# Main_PCB.net
KiCad netlist of a schematic drawn in EAGLE
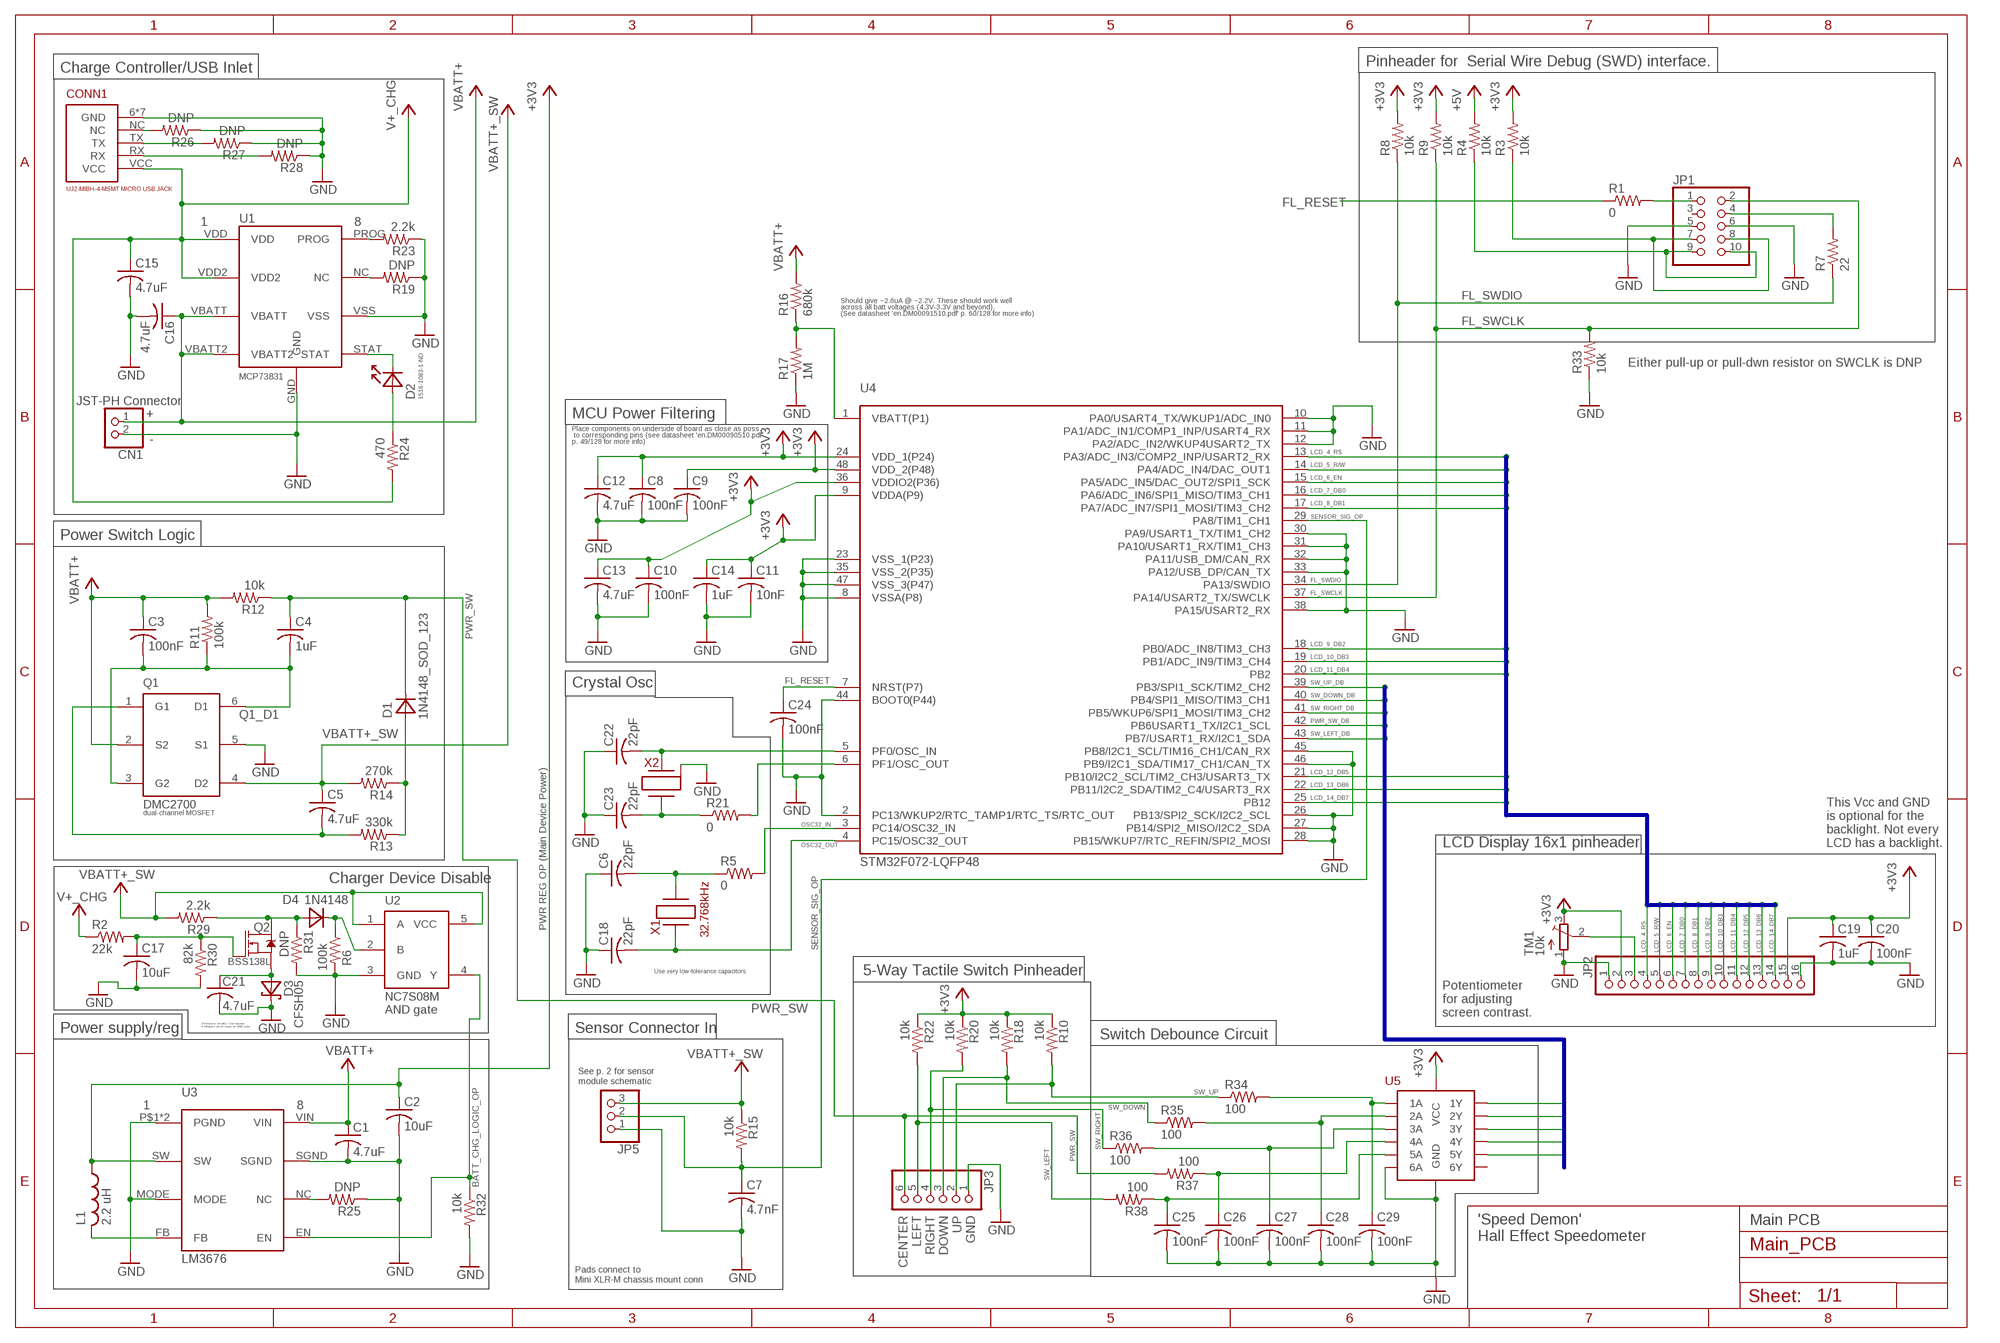
[diagram p0: schematic, sheet 1]

(export (version "E")
  (design (tool "Eeschema 10.0.6"))
  (components
    (comp (ref "C1")
      (value "4.7uF")
      (footprint "eagle-import:C_0805")
      (libsource (lib "eagle-import") (part "C_0805_NP"))
    )
    (comp (ref "C2")
      (value "10uF")
      (footprint "eagle-import:C_0805")
      (libsource (lib "eagle-import") (part "C_0805_NP"))
    )
    (comp (ref "C3")
      (value "100nF")
      (footprint "eagle-import:C_0805")
      (libsource (lib "eagle-import") (part "C_0805_NP"))
    )
    (comp (ref "C4")
      (value "1uF")
      (footprint "eagle-import:C_0805")
      (libsource (lib "eagle-import") (part "C_0805_NP"))
    )
    (comp (ref "C5")
      (value "4.7uF")
      (footprint "eagle-import:C_0805")
      (libsource (lib "eagle-import") (part "C_0805_NP"))
    )
    (comp (ref "C6")
      (value "22pF")
      (footprint "eagle-import:C_0805")
      (libsource (lib "eagle-import") (part "LCRD_SMD_generics_C_0805_NP"))
    )
    (comp (ref "C7")
      (value "4.7nF")
      (footprint "eagle-import:C_0805")
      (libsource (lib "eagle-import") (part "C_0805_NP"))
    )
    (comp (ref "C8")
      (value "100nF")
      (footprint "eagle-import:C_0805")
      (libsource (lib "eagle-import") (part "C_0805_NP"))
    )
    (comp (ref "C9")
      (value "100nF")
      (footprint "eagle-import:C_0805")
      (libsource (lib "eagle-import") (part "C_0805_NP"))
    )
    (comp (ref "C10")
      (value "100nF")
      (footprint "eagle-import:C_0805")
      (libsource (lib "eagle-import") (part "C_0805_NP"))
    )
    (comp (ref "C11")
      (value "10nF")
      (footprint "eagle-import:C_0805")
      (libsource (lib "eagle-import") (part "C_0805_NP"))
    )
    (comp (ref "C12")
      (value "4.7uF")
      (footprint "eagle-import:C_0805")
      (libsource (lib "eagle-import") (part "C_0805_NP"))
    )
    (comp (ref "C13")
      (value "4.7uF")
      (footprint "eagle-import:C_0805")
      (libsource (lib "eagle-import") (part "C_0805_NP"))
    )
    (comp (ref "C14")
      (value "1uF")
      (footprint "eagle-import:C_0805")
      (libsource (lib "eagle-import") (part "C_0805_NP"))
    )
    (comp (ref "C15")
      (value "4.7uF")
      (footprint "eagle-import:C_0805")
      (libsource (lib "eagle-import") (part "C_0805_NP"))
    )
    (comp (ref "C16")
      (value "4.7uF")
      (footprint "eagle-import:C_0805")
      (libsource (lib "eagle-import") (part "C_0805_NP"))
    )
    (comp (ref "C17")
      (value "10uF")
      (footprint "eagle-import:C_0805")
      (libsource (lib "eagle-import") (part "C_0805_NP"))
    )
    (comp (ref "C18")
      (value "22pF")
      (footprint "eagle-import:C_0805")
      (libsource (lib "eagle-import") (part "LCRD_SMD_generics_C_0805_NP"))
    )
    (comp (ref "C19")
      (value "1uF")
      (footprint "eagle-import:C_0805")
      (libsource (lib "eagle-import") (part "C_0805_NP"))
    )
    (comp (ref "C20")
      (value "100nF")
      (footprint "eagle-import:C_0805")
      (libsource (lib "eagle-import") (part "C_0805_NP"))
    )
    (comp (ref "C21")
      (value "4.7uF")
      (footprint "eagle-import:C_0805")
      (libsource (lib "eagle-import") (part "C_0805_NP"))
    )
    (comp (ref "C22")
      (value "22pF")
      (footprint "eagle-import:C_0805")
      (libsource (lib "eagle-import") (part "LCRD_SMD_generics_C_0805_NP"))
    )
    (comp (ref "C23")
      (value "22pF")
      (footprint "eagle-import:C_0805")
      (libsource (lib "eagle-import") (part "LCRD_SMD_generics_C_0805_NP"))
    )
    (comp (ref "C24")
      (value "100nF")
      (footprint "eagle-import:C_0805")
      (libsource (lib "eagle-import") (part "C_0805_NP"))
    )
    (comp (ref "C25")
      (value "100nF")
      (footprint "eagle-import:C_0805")
      (libsource (lib "eagle-import") (part "C_0805_NP"))
    )
    (comp (ref "C26")
      (value "100nF")
      (footprint "eagle-import:C_0805")
      (libsource (lib "eagle-import") (part "C_0805_NP"))
    )
    (comp (ref "C27")
      (value "100nF")
      (footprint "eagle-import:C_0805")
      (libsource (lib "eagle-import") (part "C_0805_NP"))
    )
    (comp (ref "C28")
      (value "100nF")
      (footprint "eagle-import:C_0805")
      (libsource (lib "eagle-import") (part "C_0805_NP"))
    )
    (comp (ref "C29")
      (value "100nF")
      (footprint "eagle-import:C_0805")
      (libsource (lib "eagle-import") (part "C_0805_NP"))
    )
    (comp (ref "CN1")
      (value "JST_2PIN-SMT-RA")
      (footprint "eagle-import:JST-PH-2-SMT-RA")
      (libsource (lib "eagle-import") (part "JST_2PIN-SMT-RA"))
    )
    (comp (ref "CONN1")
      (value "USB_JACK_102-4008-1-ND_USB-MICRO-B")
      (footprint "eagle-import:USB_JACK_102-4008-1-ND_UJ2-MIBH-4-MSMT-TR")
      (libsource (lib "eagle-import") (part "USB_JACK_102-4008-1-ND_USB-MICRO-B"))
    )
    (comp (ref "D1")
      (value "1N4148_SOD_123")
      (footprint "eagle-import:D_SOD_123")
      (libsource (lib "eagle-import") (part "1N4148_SOD_123"))
    )
    (comp (ref "D2")
      (value "LED_0805")
      (footprint "eagle-import:LED_0805")
      (libsource (lib "eagle-import") (part "LED_0805"))
    )
    (comp (ref "D3")
      (value "CFSH05")
      (footprint "eagle-import:SOD-882")
      (libsource (lib "eagle-import") (part "CFSH05_SCHOTTKY"))
    )
    (comp (ref "D4")
      (value "1N4148")
      (footprint "eagle-import:D_SOD_123")
      (libsource (lib "eagle-import") (part "1N4148_SOD_123"))
    )
    (comp (ref "JP1")
      (value "PINHD-2X5")
      (footprint "eagle-import:2X05")
      (libsource (lib "eagle-import") (part "PINHD-2X5"))
    )
    (comp (ref "JP2")
      (value "PINHD-1X16")
      (footprint "eagle-import:1X16")
      (libsource (lib "eagle-import") (part "PINHD-1X16"))
    )
    (comp (ref "JP3")
      (value "PINHD-1X6")
      (footprint "eagle-import:1X06")
      (libsource (lib "eagle-import") (part "PINHD-1X6"))
    )
    (comp (ref "JP5")
      (value "PINHD-1X3")
      (footprint "eagle-import:1X03")
      (libsource (lib "eagle-import") (part "PINHD-1X3"))
    )
    (comp (ref "L1")
      (value "2.2 uH")
      (footprint "eagle-import:NONSTANDARD_IND")
      (libsource (lib "eagle-import") (part "NRS4010T2R2MDGGV"))
    )
    (comp (ref "Q1")
      (value "DMC2700")
      (footprint "eagle-import:SOT-23-6")
      (libsource (lib "eagle-import") (part "DMC2700_SOT-23-6"))
    )
    (comp (ref "Q2")
      (value "BSS138L")
      (footprint "eagle-import:TO-236")
      (libsource (lib "eagle-import") (part "BSS138LT1_TO-236"))
    )
    (comp (ref "R1")
      (value "0")
      (footprint "eagle-import:R0805")
      (libsource (lib "eagle-import") (part "R-US_R0805"))
    )
    (comp (ref "R2")
      (value "22k")
      (footprint "eagle-import:R_0805")
      (libsource (lib "eagle-import") (part "R_0805"))
    )
    (comp (ref "R3")
      (value "10k")
      (footprint "eagle-import:R0805")
      (libsource (lib "eagle-import") (part "R-US_R0805"))
    )
    (comp (ref "R4")
      (value "10k")
      (footprint "eagle-import:R0805")
      (libsource (lib "eagle-import") (part "R-US_R0805"))
    )
    (comp (ref "R5")
      (value "0")
      (footprint "eagle-import:R0805")
      (libsource (lib "eagle-import") (part "R-US_R0805"))
    )
    (comp (ref "R6")
      (value "100k")
      (footprint "eagle-import:R_0805")
      (libsource (lib "eagle-import") (part "R_0805"))
    )
    (comp (ref "R7")
      (value "22")
      (footprint "eagle-import:R0805")
      (libsource (lib "eagle-import") (part "R-US_R0805"))
    )
    (comp (ref "R8")
      (value "10k")
      (footprint "eagle-import:R0805")
      (libsource (lib "eagle-import") (part "R-US_R0805"))
    )
    (comp (ref "R9")
      (value "10k")
      (footprint "eagle-import:R0805")
      (libsource (lib "eagle-import") (part "R-US_R0805"))
    )
    (comp (ref "R10")
      (value "10k")
      (footprint "eagle-import:R_0805")
      (libsource (lib "eagle-import") (part "R_0805"))
    )
    (comp (ref "R11")
      (value "100k")
      (footprint "eagle-import:R_0805")
      (libsource (lib "eagle-import") (part "R_0805"))
    )
    (comp (ref "R12")
      (value "10k")
      (footprint "eagle-import:R_0805")
      (libsource (lib "eagle-import") (part "R_0805"))
    )
    (comp (ref "R13")
      (value "330k")
      (footprint "eagle-import:R_0805")
      (libsource (lib "eagle-import") (part "R_0805"))
    )
    (comp (ref "R14")
      (value "270k")
      (footprint "eagle-import:R_0805")
      (libsource (lib "eagle-import") (part "R_0805"))
    )
    (comp (ref "R15")
      (value "10k")
      (footprint "eagle-import:R_0805")
      (libsource (lib "eagle-import") (part "R_0805"))
    )
    (comp (ref "R16")
      (value "680k")
      (footprint "eagle-import:R_0805")
      (libsource (lib "eagle-import") (part "R_0805"))
    )
    (comp (ref "R17")
      (value "1M")
      (footprint "eagle-import:R_0805")
      (libsource (lib "eagle-import") (part "R_0805"))
    )
    (comp (ref "R18")
      (value "10k")
      (footprint "eagle-import:R_0805")
      (libsource (lib "eagle-import") (part "R_0805"))
    )
    (comp (ref "R19")
      (value "DNP")
      (footprint "eagle-import:R_0805")
      (libsource (lib "eagle-import") (part "R_0805"))
    )
    (comp (ref "R20")
      (value "10k")
      (footprint "eagle-import:R_0805")
      (libsource (lib "eagle-import") (part "R_0805"))
    )
    (comp (ref "R21")
      (value "0")
      (footprint "eagle-import:R_0805")
      (libsource (lib "eagle-import") (part "LCRD_SMD_generics_R_0805"))
    )
    (comp (ref "R22")
      (value "10k")
      (footprint "eagle-import:R_0805")
      (libsource (lib "eagle-import") (part "R_0805"))
    )
    (comp (ref "R23")
      (value "2.2k")
      (footprint "eagle-import:R_0805")
      (libsource (lib "eagle-import") (part "R_0805"))
    )
    (comp (ref "R24")
      (value "470")
      (footprint "eagle-import:R_0805")
      (libsource (lib "eagle-import") (part "R_0805"))
    )
    (comp (ref "R25")
      (value "DNP")
      (footprint "eagle-import:R_0805")
      (libsource (lib "eagle-import") (part "R_0805"))
    )
    (comp (ref "R26")
      (value "DNP")
      (footprint "eagle-import:R_0805")
      (libsource (lib "eagle-import") (part "R_0805"))
    )
    (comp (ref "R27")
      (value "DNP")
      (footprint "eagle-import:R_0805")
      (libsource (lib "eagle-import") (part "R_0805"))
    )
    (comp (ref "R28")
      (value "DNP")
      (footprint "eagle-import:R_0805")
      (libsource (lib "eagle-import") (part "R_0805"))
    )
    (comp (ref "R29")
      (value "2.2k")
      (footprint "eagle-import:R_0805")
      (libsource (lib "eagle-import") (part "R_0805"))
    )
    (comp (ref "R30")
      (value "82k")
      (footprint "eagle-import:R_0805")
      (libsource (lib "eagle-import") (part "R_0805"))
    )
    (comp (ref "R31")
      (value "DNP")
      (footprint "eagle-import:R_0805")
      (libsource (lib "eagle-import") (part "R_0805"))
    )
    (comp (ref "R32")
      (value "10k")
      (footprint "eagle-import:R_0805")
      (libsource (lib "eagle-import") (part "R_0805"))
    )
    (comp (ref "R33")
      (value "10k")
      (footprint "eagle-import:R0805")
      (libsource (lib "eagle-import") (part "R-US_R0805"))
    )
    (comp (ref "R34")
      (value "100")
      (footprint "eagle-import:R_0805")
      (libsource (lib "eagle-import") (part "R_0805"))
    )
    (comp (ref "R35")
      (value "100")
      (footprint "eagle-import:R_0805")
      (libsource (lib "eagle-import") (part "R_0805"))
    )
    (comp (ref "R36")
      (value "100")
      (footprint "eagle-import:R_0805")
      (libsource (lib "eagle-import") (part "R_0805"))
    )
    (comp (ref "R37")
      (value "100")
      (footprint "eagle-import:R_0805")
      (libsource (lib "eagle-import") (part "R_0805"))
    )
    (comp (ref "R38")
      (value "100")
      (footprint "eagle-import:R_0805")
      (libsource (lib "eagle-import") (part "R_0805"))
    )
    (comp (ref "TM1")
      (value "10k")
      (footprint "eagle-import:TRIM-3386")
      (libsource (lib "eagle-import") (part "TRIMPOT3386"))
    )
    (comp (ref "U1")
      (value "MCP73831_8-DFN")
      (footprint "eagle-import:8-DFN-(2X3)")
      (libsource (lib "eagle-import") (part "MCP73831_8-DFN"))
    )
    (comp (ref "U2")
      (value "NC7S08M")
      (footprint "eagle-import:SOT-23-5")
      (libsource (lib "eagle-import") (part "NC7S08_SOT_23_5"))
    )
    (comp (ref "U3")
      (value "LM3676")
      (footprint "eagle-import:WSON")
      (libsource (lib "eagle-import") (part "LM3676"))
    )
    (comp (ref "U4")
      (value "STM32F072-LQFP48")
      (footprint "eagle-import:LQFP48")
      (libsource (lib "eagle-import") (part "STM32F072-LQFP48"))
    )
    (comp (ref "U5")
      (value "SN74LV14A_HEX_SHMITT")
      (footprint "eagle-import:S-PVFQN-N14")
      (libsource (lib "eagle-import") (part "SN74LV14A_HEX_SHMITT"))
    )
    (comp (ref "X1")
      (value "32.768kHz")
      (footprint "eagle-import:CRYSTAL_OSC_3.2X1.5")
      (libsource (lib "eagle-import") (part "XC2292CT-ND"))
    )
    (comp (ref "X2")
      (value "ABM3B-8.000MHZ-10-D-1-G-T")
      (footprint "eagle-import:4-SMD")
      (libsource (lib "eagle-import") (part "ABM3B-8.000MHZ-10-D-1-G-T"))
    )
  )
  (nets
    (net (code "1") (name "+3V3") (class "Default")
      (node (ref "C10") (pin "1") (pinfunction "1_1") (pintype "passive"))
      (node (ref "C11") (pin "1") (pinfunction "1_1") (pintype "passive"))
      (node (ref "C12") (pin "1") (pinfunction "1_1") (pintype "passive"))
      (node (ref "C13") (pin "1") (pinfunction "1_1") (pintype "passive"))
      (node (ref "C14") (pin "1") (pinfunction "1_1") (pintype "passive"))
      (node (ref "C19") (pin "1") (pinfunction "1_1") (pintype "passive"))
      (node (ref "C2") (pin "1") (pinfunction "1_1") (pintype "passive"))
      (node (ref "C20") (pin "1") (pinfunction "1_1") (pintype "passive"))
      (node (ref "C8") (pin "1") (pinfunction "1_1") (pintype "passive"))
      (node (ref "C9") (pin "1") (pinfunction "1_1") (pintype "passive"))
      (node (ref "JP2") (pin "15") (pinfunction "15_15") (pintype "passive"))
      (node (ref "JP2") (pin "2") (pinfunction "2_2") (pintype "passive"))
      (node (ref "L1") (pin "P$1") (pinfunction "1_P$1") (pintype "passive"))
      (node (ref "R10") (pin "1") (pinfunction "1_1") (pintype "passive"))
      (node (ref "R18") (pin "1") (pinfunction "1_1") (pintype "passive"))
      (node (ref "R20") (pin "1") (pinfunction "1_1") (pintype "passive"))
      (node (ref "R22") (pin "1") (pinfunction "1_1") (pintype "passive"))
      (node (ref "R3") (pin "2") (pinfunction "2_2") (pintype "passive"))
      (node (ref "R8") (pin "2") (pinfunction "2_2") (pintype "passive"))
      (node (ref "R9") (pin "2") (pinfunction "2_2") (pintype "passive"))
      (node (ref "TM1") (pin "3") (pinfunction "E_3") (pintype "passive"))
      (node (ref "U3") (pin "SW") (pinfunction "SW_SW") (pintype "bidirectional"))
      (node (ref "U4") (pin "24") (pinfunction "VDD_1(P24)_24") (pintype "bidirectional"))
      (node (ref "U4") (pin "36") (pinfunction "VDDIO2(P36)_36") (pintype "bidirectional"))
      (node (ref "U4") (pin "48") (pinfunction "VDD_2(P48)_48") (pintype "bidirectional"))
      (node (ref "U4") (pin "9") (pinfunction "VDDA(P9)_9") (pintype "bidirectional"))
      (node (ref "U5") (pin "P$14") (pinfunction "VCC_P$14") (pintype "power_in"))
    )
    (net (code "2") (name "+5V") (class "Default")
      (node (ref "R4") (pin "2") (pinfunction "2_2") (pintype "passive"))
    )
    (net (code "3") (name "/BATT_CHG_LOGIC_OP") (class "Default")
      (node (ref "R32") (pin "1") (pinfunction "1_1") (pintype "passive"))
      (node (ref "U2") (pin "4") (pinfunction "Y_4") (pintype "bidirectional"))
      (node (ref "U3") (pin "EN") (pinfunction "EN_EN") (pintype "bidirectional"))
    )
    (net (code "4") (name "/FL_RESET") (class "Default")
      (node (ref "C24") (pin "1") (pinfunction "1_1") (pintype "passive"))
      (node (ref "R1") (pin "1") (pinfunction "1_1") (pintype "passive"))
      (node (ref "U4") (pin "7") (pinfunction "NRST(P7)_7") (pintype "bidirectional"))
    )
    (net (code "5") (name "/FL_SWCLK") (class "Default")
      (node (ref "JP1") (pin "2") (pinfunction "2_2") (pintype "passive"))
      (node (ref "R33") (pin "2") (pinfunction "2_2") (pintype "passive"))
      (node (ref "R9") (pin "1") (pinfunction "1_1") (pintype "passive"))
      (node (ref "U4") (pin "37") (pinfunction "PA14/USART2_TX/SWCLK_37") (pintype "bidirectional"))
    )
    (net (code "6") (name "/FL_SWDIO") (class "Default")
      (node (ref "R7") (pin "1") (pinfunction "1_1") (pintype "passive"))
      (node (ref "R8") (pin "1") (pinfunction "1_1") (pintype "passive"))
      (node (ref "U4") (pin "34") (pinfunction "PA13/SWDIO_34") (pintype "bidirectional"))
    )
    (net (code "7") (name "/LCD_4_RS") (class "Default")
      (node (ref "JP2") (pin "4") (pinfunction "4_4") (pintype "passive"))
      (node (ref "U4") (pin "13") (pinfunction "PA3/ADC_IN3/COMP2_INP/USART2_RX_13") (pintype "bidirectional"))
    )
    (net (code "8") (name "/LCD_5_R{slash}W") (class "Default")
      (node (ref "JP2") (pin "5") (pinfunction "5_5") (pintype "passive"))
      (node (ref "U4") (pin "14") (pinfunction "PA4/ADC_IN4/DAC_OUT1_14") (pintype "bidirectional"))
    )
    (net (code "9") (name "/LCD_6_EN") (class "Default")
      (node (ref "JP2") (pin "6") (pinfunction "6_6") (pintype "passive"))
      (node (ref "U4") (pin "15") (pinfunction "PA5/ADC_IN5/DAC_OUT2/SPI1_SCK_15") (pintype "bidirectional"))
    )
    (net (code "10") (name "/LCD_7_DB0") (class "Default")
      (node (ref "JP2") (pin "7") (pinfunction "7_7") (pintype "passive"))
      (node (ref "U4") (pin "16") (pinfunction "PA6/ADC_IN6/SPI1_MISO/TIM3_CH1_16") (pintype "bidirectional"))
    )
    (net (code "11") (name "/LCD_8_DB1") (class "Default")
      (node (ref "JP2") (pin "8") (pinfunction "8_8") (pintype "passive"))
      (node (ref "U4") (pin "17") (pinfunction "PA7/ADC_IN7/SPI1_MOSI/TIM3_CH2_17") (pintype "bidirectional"))
    )
    (net (code "12") (name "/LCD_9_DB2") (class "Default")
      (node (ref "JP2") (pin "9") (pinfunction "9_9") (pintype "passive"))
      (node (ref "U4") (pin "18") (pinfunction "PB0/ADC_IN8/TIM3_CH3_18") (pintype "bidirectional"))
    )
    (net (code "13") (name "/LCD_10_DB3") (class "Default")
      (node (ref "JP2") (pin "10") (pinfunction "10_10") (pintype "passive"))
      (node (ref "U4") (pin "19") (pinfunction "PB1/ADC_IN9/TIM3_CH4_19") (pintype "bidirectional"))
    )
    (net (code "14") (name "/LCD_11_DB4") (class "Default")
      (node (ref "JP2") (pin "11") (pinfunction "11_11") (pintype "passive"))
      (node (ref "U4") (pin "20") (pinfunction "PB2_20") (pintype "bidirectional"))
    )
    (net (code "15") (name "/LCD_12_DB5") (class "Default")
      (node (ref "JP2") (pin "12") (pinfunction "12_12") (pintype "passive"))
      (node (ref "U4") (pin "21") (pinfunction "PB10/I2C2_SCL/TIM2_CH3/USART3_TX_21") (pintype "bidirectional"))
    )
    (net (code "16") (name "/LCD_13_DB6") (class "Default")
      (node (ref "JP2") (pin "13") (pinfunction "13_13") (pintype "passive"))
      (node (ref "U4") (pin "22") (pinfunction "PB11/I2C2_SDA/TIM2_C4/USART3_RX_22") (pintype "bidirectional"))
    )
    (net (code "17") (name "/LCD_14_DB7") (class "Default")
      (node (ref "JP2") (pin "14") (pinfunction "14_14") (pintype "passive"))
      (node (ref "U4") (pin "25") (pinfunction "PB12_25") (pintype "bidirectional"))
    )
    (net (code "18") (name "/OSC32_IN") (class "Default")
      (node (ref "C6") (pin "2") (pinfunction "2_2") (pintype "passive"))
      (node (ref "R5") (pin "1") (pinfunction "1_1") (pintype "passive"))
      (node (ref "X1") (pin "P$1") (pinfunction "1_P$1") (pintype "bidirectional"))
    )
    (net (code "19") (name "/OSC32_OUT") (class "Default")
      (node (ref "C18") (pin "2") (pinfunction "2_2") (pintype "passive"))
      (node (ref "U4") (pin "4") (pinfunction "PC15/OSC32_OUT_4") (pintype "bidirectional"))
      (node (ref "X1") (pin "P$2") (pinfunction "2_P$2") (pintype "bidirectional"))
    )
    (net (code "20") (name "/PWR_SW") (class "Default")
      (node (ref "C4") (pin "1") (pinfunction "1_1") (pintype "passive"))
      (node (ref "D1") (pin "2") (pinfunction "C_2") (pintype "passive"))
      (node (ref "JP3") (pin "6") (pinfunction "6_6") (pintype "passive"))
      (node (ref "R12") (pin "1") (pinfunction "1_1") (pintype "passive"))
      (node (ref "R37") (pin "2") (pinfunction "2_2") (pintype "passive"))
    )
    (net (code "21") (name "/PWR_SW_DB") (class "Default")
      (node (ref "U4") (pin "42") (pinfunction "PB6USART1_TX/I2C1_SCL_42") (pintype "bidirectional"))
      (node (ref "U5") (pin "P$8") (pinfunction "4Y_P$8") (pintype "bidirectional"))
    )
    (net (code "22") (name "/Q1_D1") (class "Default")
      (node (ref "C3") (pin "2") (pinfunction "2_2") (pintype "passive"))
      (node (ref "C4") (pin "2") (pinfunction "2_2") (pintype "passive"))
      (node (ref "Q1") (pin "3") (pinfunction "G2_3") (pintype "bidirectional"))
      (node (ref "Q1") (pin "6") (pinfunction "D1_6") (pintype "bidirectional"))
      (node (ref "R11") (pin "1") (pinfunction "1_1") (pintype "passive"))
    )
    (net (code "23") (name "/SENSOR_SIG_OP") (class "Default")
      (node (ref "C7") (pin "1") (pinfunction "1_1") (pintype "passive"))
      (node (ref "JP5") (pin "2") (pinfunction "2_2") (pintype "passive"))
      (node (ref "R15") (pin "2") (pinfunction "2_2") (pintype "passive"))
      (node (ref "U4") (pin "29") (pinfunction "PA8/TIM1_CH1_29") (pintype "bidirectional"))
    )
    (net (code "24") (name "/SW_DOWN") (class "Default")
      (node (ref "JP3") (pin "3") (pinfunction "3_3") (pintype "passive"))
      (node (ref "R18") (pin "2") (pinfunction "2_2") (pintype "passive"))
      (node (ref "R35") (pin "1") (pinfunction "1_1") (pintype "passive"))
    )
    (net (code "25") (name "/SW_DOWN_DB") (class "Default")
      (node (ref "U4") (pin "40") (pinfunction "PB4/SPI1_MISO/TIM3_CH1_40") (pintype "bidirectional"))
      (node (ref "U5") (pin "P$4") (pinfunction "2Y_P$4") (pintype "bidirectional"))
    )
    (net (code "26") (name "/SW_LEFT") (class "Default")
      (node (ref "JP3") (pin "5") (pinfunction "5_5") (pintype "passive"))
      (node (ref "R22") (pin "2") (pinfunction "2_2") (pintype "passive"))
      (node (ref "R38") (pin "2") (pinfunction "2_2") (pintype "passive"))
    )
    (net (code "27") (name "/SW_LEFT_DB") (class "Default")
      (node (ref "U4") (pin "43") (pinfunction "PB7/USART1_RX/I2C1_SDA_43") (pintype "bidirectional"))
      (node (ref "U5") (pin "P$10") (pinfunction "5Y_P$10") (pintype "bidirectional"))
    )
    (net (code "28") (name "/SW_RIGHT") (class "Default")
      (node (ref "JP3") (pin "4") (pinfunction "4_4") (pintype "passive"))
      (node (ref "R20") (pin "2") (pinfunction "2_2") (pintype "passive"))
      (node (ref "R36") (pin "1") (pinfunction "1_1") (pintype "passive"))
    )
    (net (code "29") (name "/SW_RIGHT_DB") (class "Default")
      (node (ref "U4") (pin "41") (pinfunction "PB5/WKUP6/SPI1_MOSI/TIM3_CH2_41") (pintype "bidirectional"))
      (node (ref "U5") (pin "P$6") (pinfunction "3Y_P$6") (pintype "bidirectional"))
    )
    (net (code "30") (name "/SW_UP") (class "Default")
      (node (ref "JP3") (pin "2") (pinfunction "2_2") (pintype "passive"))
      (node (ref "R10") (pin "2") (pinfunction "2_2") (pintype "passive"))
      (node (ref "R34") (pin "1") (pinfunction "1_1") (pintype "passive"))
    )
    (net (code "31") (name "/SW_UP_DB") (class "Default")
      (node (ref "U4") (pin "39") (pinfunction "PB3/SPI1_SCK/TIM2_CH2_39") (pintype "bidirectional"))
      (node (ref "U5") (pin "P$2") (pinfunction "1Y_P$2") (pintype "bidirectional"))
    )
    (net (code "32") (name "GND") (class "Default")
      (node (ref "C1") (pin "2") (pinfunction "2_2") (pintype "passive"))
      (node (ref "C10") (pin "2") (pinfunction "2_2") (pintype "passive"))
      (node (ref "C11") (pin "2") (pinfunction "2_2") (pintype "passive"))
      (node (ref "C12") (pin "2") (pinfunction "2_2") (pintype "passive"))
      (node (ref "C13") (pin "2") (pinfunction "2_2") (pintype "passive"))
      (node (ref "C14") (pin "2") (pinfunction "2_2") (pintype "passive"))
      (node (ref "C15") (pin "2") (pinfunction "2_2") (pintype "passive"))
      (node (ref "C16") (pin "2") (pinfunction "2_2") (pintype "passive"))
      (node (ref "C17") (pin "2") (pinfunction "2_2") (pintype "passive"))
      (node (ref "C18") (pin "1") (pinfunction "1_1") (pintype "passive"))
      (node (ref "C19") (pin "2") (pinfunction "2_2") (pintype "passive"))
      (node (ref "C2") (pin "2") (pinfunction "2_2") (pintype "passive"))
      (node (ref "C20") (pin "2") (pinfunction "2_2") (pintype "passive"))
      (node (ref "C21") (pin "2") (pinfunction "2_2") (pintype "passive"))
      (node (ref "C22") (pin "1") (pinfunction "1_1") (pintype "passive"))
      (node (ref "C23") (pin "1") (pinfunction "1_1") (pintype "passive"))
      (node (ref "C24") (pin "2") (pinfunction "2_2") (pintype "passive"))
      (node (ref "C25") (pin "2") (pinfunction "2_2") (pintype "passive"))
      (node (ref "C26") (pin "2") (pinfunction "2_2") (pintype "passive"))
      (node (ref "C27") (pin "2") (pinfunction "2_2") (pintype "passive"))
      (node (ref "C28") (pin "2") (pinfunction "2_2") (pintype "passive"))
      (node (ref "C29") (pin "2") (pinfunction "2_2") (pintype "passive"))
      (node (ref "C6") (pin "1") (pinfunction "1_1") (pintype "passive"))
      (node (ref "C7") (pin "2") (pinfunction "2_2") (pintype "passive"))
      (node (ref "C8") (pin "2") (pinfunction "2_2") (pintype "passive"))
      (node (ref "C9") (pin "2") (pinfunction "2_2") (pintype "passive"))
      (node (ref "CN1") (pin "2") (pinfunction "1_2") (pintype "passive"))
      (node (ref "CONN1") (pin "10") (pinfunction "GND_10") (pintype "bidirectional"))
      (node (ref "CONN1") (pin "11") (pinfunction "GND_11") (pintype "bidirectional"))
      (node (ref "CONN1") (pin "6") (pinfunction "GND_6") (pintype "bidirectional"))
      (node (ref "CONN1") (pin "7") (pinfunction "GND_7") (pintype "bidirectional"))
      (node (ref "CONN1") (pin "8") (pinfunction "GND_8") (pintype "bidirectional"))
      (node (ref "CONN1") (pin "9") (pinfunction "GND_9") (pintype "bidirectional"))
      (node (ref "CONN1") (pin "GND") (pinfunction "GND_GND") (pintype "bidirectional"))
      (node (ref "D3") (pin "P$2") (pinfunction "C_P$2") (pintype "passive"))
      (node (ref "JP1") (pin "5") (pinfunction "5_5") (pintype "passive"))
      (node (ref "JP1") (pin "6") (pinfunction "6_6") (pintype "passive"))
      (node (ref "JP2") (pin "1") (pinfunction "1_1") (pintype "passive"))
      (node (ref "JP2") (pin "16") (pinfunction "16_16") (pintype "passive"))
      (node (ref "JP3") (pin "1") (pinfunction "1_1") (pintype "passive"))
      (node (ref "JP5") (pin "1") (pinfunction "1_1") (pintype "passive"))
      (node (ref "Q1") (pin "5") (pinfunction "S1_5") (pintype "bidirectional"))
      (node (ref "R17") (pin "1") (pinfunction "1_1") (pintype "passive"))
      (node (ref "R19") (pin "1") (pinfunction "1_1") (pintype "passive"))
      (node (ref "R23") (pin "1") (pinfunction "1_1") (pintype "passive"))
      (node (ref "R25") (pin "1") (pinfunction "1_1") (pintype "passive"))
      (node (ref "R26") (pin "1") (pinfunction "1_1") (pintype "passive"))
      (node (ref "R27") (pin "1") (pinfunction "1_1") (pintype "passive"))
      (node (ref "R28") (pin "1") (pinfunction "1_1") (pintype "passive"))
      (node (ref "R30") (pin "2") (pinfunction "2_2") (pintype "passive"))
      (node (ref "R31") (pin "2") (pinfunction "2_2") (pintype "passive"))
      (node (ref "R32") (pin "2") (pinfunction "2_2") (pintype "passive"))
      (node (ref "R33") (pin "1") (pinfunction "1_1") (pintype "passive"))
      (node (ref "R6") (pin "2") (pinfunction "2_2") (pintype "passive"))
      (node (ref "TM1") (pin "1") (pinfunction "A_1") (pintype "passive"))
      (node (ref "U1") (pin "GND") (pinfunction "GND_GND") (pintype "bidirectional"))
      (node (ref "U1") (pin "VSS") (pinfunction "VSS_VSS") (pintype "bidirectional"))
      (node (ref "U2") (pin "3") (pinfunction "GND_3") (pintype "bidirectional"))
      (node (ref "U3") (pin "MODE") (pinfunction "MODE_MODE") (pintype "bidirectional"))
      (node (ref "U3") (pin "P$1") (pinfunction "PGND_P$1") (pintype "power_in"))
      (node (ref "U3") (pin "PGND") (pinfunction "PGND_PGND") (pintype "power_in"))
      (node (ref "U3") (pin "SGND") (pinfunction "SGND_SGND") (pintype "power_in"))
      (node (ref "U4") (pin "10") (pinfunction "PA0/USART4_TX/WKUP1/ADC_IN0_10") (pintype "bidirectional"))
      (node (ref "U4") (pin "11") (pinfunction "PA1/ADC_IN1/COMP1_INP/USART4_RX_11") (pintype "bidirectional"))
      (node (ref "U4") (pin "12") (pinfunction "PA2/ADC_IN2/WKUP4USART2_TX_12") (pintype "bidirectional"))
      (node (ref "U4") (pin "2") (pinfunction "PC13/WKUP2/RTC_TAMP1/RTC_TS/RTC_OUT_2") (pintype "bidirectional"))
      (node (ref "U4") (pin "23") (pinfunction "VSS_1(P23)_23") (pintype "bidirectional"))
      (node (ref "U4") (pin "26") (pinfunction "PB13/SPI2_SCK/I2C2_SCL_26") (pintype "bidirectional"))
      (node (ref "U4") (pin "27") (pinfunction "PB14/SPI2_MISO/I2C2_SDA_27") (pintype "bidirectional"))
      (node (ref "U4") (pin "28") (pinfunction "PB15/WKUP7/RTC_REFIN/SPI2_MOSI_28") (pintype "bidirectional"))
      (node (ref "U4") (pin "30") (pinfunction "PA9/USART1_TX/TIM1_CH2_30") (pintype "bidirectional"))
      (node (ref "U4") (pin "31") (pinfunction "PA10/USART1_RX/TIM1_CH3_31") (pintype "bidirectional"))
      (node (ref "U4") (pin "32") (pinfunction "PA11/USB_DM/CAN_RX_32") (pintype "bidirectional"))
      (node (ref "U4") (pin "33") (pinfunction "PA12/USB_DP/CAN_TX_33") (pintype "bidirectional"))
      (node (ref "U4") (pin "35") (pinfunction "VSS_2(P35)_35") (pintype "bidirectional"))
      (node (ref "U4") (pin "38") (pinfunction "PA15/USART2_RX_38") (pintype "bidirectional"))
      (node (ref "U4") (pin "44") (pinfunction "BOOT0(P44)_44") (pintype "bidirectional"))
      (node (ref "U4") (pin "45") (pinfunction "PB8/I2C1_SCL/TIM16_CH1/CAN_RX_45") (pintype "bidirectional"))
      (node (ref "U4") (pin "46") (pinfunction "PB9/I2C1_SDA/TIM17_CH1/CAN_TX_46") (pintype "bidirectional"))
      (node (ref "U4") (pin "47") (pinfunction "VSS_3(P47)_47") (pintype "bidirectional"))
      (node (ref "U4") (pin "8") (pinfunction "VSSA(P8)_8") (pintype "bidirectional"))
      (node (ref "U5") (pin "GND") (pinfunction "GND_GND") (pintype "power_in"))
      (node (ref "U5") (pin "P$13") (pinfunction "6A_P$13") (pintype "bidirectional"))
      (node (ref "U5") (pin "P$7") (pinfunction "GND_P$7") (pintype "power_in"))
      (node (ref "X2") (pin "P$02") (pinfunction "P$1_P$02") (pintype "bidirectional"))
      (node (ref "X2") (pin "P$04") (pinfunction "P$1_P$04") (pintype "bidirectional"))
    )
    (net (code "33") (name "Net-(CONN1-PadNC)") (class "Default")
      (node (ref "CONN1") (pin "NC") (pinfunction "NC_NC") (pintype "bidirectional"))
      (node (ref "R26") (pin "2") (pinfunction "2_2") (pintype "passive"))
    )
    (net (code "34") (name "Net-(CONN1-PadRX)") (class "Default")
      (node (ref "CONN1") (pin "RX") (pinfunction "RX_RX") (pintype "bidirectional"))
      (node (ref "R28") (pin "2") (pinfunction "2_2") (pintype "passive"))
    )
    (net (code "35") (name "Net-(CONN1-PadTX)") (class "Default")
      (node (ref "CONN1") (pin "TX") (pinfunction "TX_TX") (pintype "bidirectional"))
      (node (ref "R27") (pin "2") (pinfunction "2_2") (pintype "passive"))
    )
    (net (code "36") (name "Net-(D1-A)") (class "Default")
      (node (ref "D1") (pin "1") (pinfunction "A_1") (pintype "passive"))
      (node (ref "R13") (pin "1") (pinfunction "1_1") (pintype "passive"))
      (node (ref "R14") (pin "1") (pinfunction "1_1") (pintype "passive"))
    )
    (net (code "37") (name "Net-(D2-A)") (class "Default")
      (node (ref "D2") (pin "1") (pinfunction "A_1") (pintype "passive"))
      (node (ref "R24") (pin "1") (pinfunction "1_1") (pintype "passive"))
    )
    (net (code "38") (name "Net-(D2-C)") (class "Default")
      (node (ref "D2") (pin "2") (pinfunction "C_2") (pintype "passive"))
      (node (ref "U1") (pin "STAT") (pinfunction "STAT_STAT") (pintype "bidirectional"))
    )
    (net (code "39") (name "Net-(D3-A)") (class "Default")
      (node (ref "C21") (pin "1") (pinfunction "1_1") (pintype "passive"))
      (node (ref "D3") (pin "P$1") (pinfunction "A_P$1") (pintype "passive"))
      (node (ref "Q2") (pin "2") (pinfunction "S_2") (pintype "bidirectional"))
    )
    (net (code "40") (name "Net-(D4-A)") (class "Default")
      (node (ref "D4") (pin "1") (pinfunction "A_1") (pintype "passive"))
      (node (ref "Q2") (pin "3") (pinfunction "D_3") (pintype "bidirectional"))
      (node (ref "R29") (pin "1") (pinfunction "1_1") (pintype "passive"))
      (node (ref "R31") (pin "1") (pinfunction "1_1") (pintype "passive"))
    )
    (net (code "41") (name "Net-(D4-C)") (class "Default")
      (node (ref "D4") (pin "2") (pinfunction "C_2") (pintype "passive"))
      (node (ref "R6") (pin "1") (pinfunction "1_1") (pintype "passive"))
      (node (ref "U2") (pin "2") (pinfunction "B_2") (pintype "bidirectional"))
    )
    (net (code "42") (name "Net-(JP1-Pad1)") (class "Default")
      (node (ref "JP1") (pin "1") (pinfunction "1_1") (pintype "passive"))
      (node (ref "R1") (pin "2") (pinfunction "2_2") (pintype "passive"))
    )
    (net (code "43") (name "Net-(JP1-Pad4)") (class "Default")
      (node (ref "JP1") (pin "4") (pinfunction "4_4") (pintype "passive"))
      (node (ref "R7") (pin "2") (pinfunction "2_2") (pintype "passive"))
    )
    (net (code "44") (name "Net-(JP1-Pad7)") (class "Default")
      (node (ref "JP1") (pin "7") (pinfunction "7_7") (pintype "passive"))
      (node (ref "JP1") (pin "8") (pinfunction "8_8") (pintype "passive"))
      (node (ref "R3") (pin "1") (pinfunction "1_1") (pintype "passive"))
    )
    (net (code "45") (name "Net-(JP1-Pad10)") (class "Default")
      (node (ref "JP1") (pin "10") (pinfunction "10_10") (pintype "passive"))
      (node (ref "JP1") (pin "9") (pinfunction "9_9") (pintype "passive"))
      (node (ref "R4") (pin "1") (pinfunction "1_1") (pintype "passive"))
    )
    (net (code "46") (name "Net-(L1-2)") (class "Default")
      (node (ref "L1") (pin "P$2") (pinfunction "2_P$2") (pintype "passive"))
      (node (ref "U3") (pin "FB") (pinfunction "FB_FB") (pintype "bidirectional"))
    )
    (net (code "47") (name "Net-(Q1-G1)") (class "Default")
      (node (ref "C5") (pin "2") (pinfunction "2_2") (pintype "passive"))
      (node (ref "Q1") (pin "1") (pinfunction "G1_1") (pintype "bidirectional"))
      (node (ref "R13") (pin "2") (pinfunction "2_2") (pintype "passive"))
    )
    (net (code "48") (name "Net-(Q2-G)") (class "Default")
      (node (ref "C17") (pin "1") (pinfunction "1_1") (pintype "passive"))
      (node (ref "Q2") (pin "1") (pinfunction "G_1") (pintype "bidirectional"))
      (node (ref "R2") (pin "2") (pinfunction "2_2") (pintype "passive"))
      (node (ref "R30") (pin "1") (pinfunction "1_1") (pintype "passive"))
    )
    (net (code "49") (name "Net-(R19-Pad2)") (class "Default")
      (node (ref "R19") (pin "2") (pinfunction "2_2") (pintype "passive"))
      (node (ref "U1") (pin "NC") (pinfunction "NC_NC") (pintype "power_in"))
    )
    (net (code "50") (name "Net-(R23-Pad2)") (class "Default")
      (node (ref "R23") (pin "2") (pinfunction "2_2") (pintype "passive"))
      (node (ref "U1") (pin "PROG") (pinfunction "PROG_PROG") (pintype "bidirectional"))
    )
    (net (code "51") (name "Net-(R25-Pad2)") (class "Default")
      (node (ref "R25") (pin "2") (pinfunction "2_2") (pintype "passive"))
      (node (ref "U3") (pin "NC") (pinfunction "NC_NC") (pintype "bidirectional"))
    )
    (net (code "52") (name "Net-(TM1-S)") (class "Default")
      (node (ref "JP2") (pin "3") (pinfunction "3_3") (pintype "passive"))
      (node (ref "TM1") (pin "2") (pinfunction "S_2") (pintype "passive"))
    )
    (net (code "53") (name "Net-(U4-PC14{slash}OSC32_IN)") (class "Default")
      (node (ref "R5") (pin "2") (pinfunction "2_2") (pintype "passive"))
      (node (ref "U4") (pin "3") (pinfunction "PC14/OSC32_IN_3") (pintype "bidirectional"))
    )
    (net (code "54") (name "Net-(U4-PF0{slash}OSC_IN)") (class "Default")
      (node (ref "C22") (pin "2") (pinfunction "2_2") (pintype "passive"))
      (node (ref "U4") (pin "5") (pinfunction "PF0/OSC_IN_5") (pintype "bidirectional"))
      (node (ref "X2") (pin "P$01") (pinfunction "1_P$01") (pintype "bidirectional"))
    )
    (net (code "55") (name "Net-(U4-PF1{slash}OSC_OUT)") (class "Default")
      (node (ref "R21") (pin "2") (pinfunction "2_2") (pintype "passive"))
      (node (ref "U4") (pin "6") (pinfunction "PF1/OSC_OUT_6") (pintype "bidirectional"))
    )
    (net (code "56") (name "Net-(U4-VBATT(P1))") (class "Default")
      (node (ref "R16") (pin "1") (pinfunction "1_1") (pintype "passive"))
      (node (ref "R17") (pin "2") (pinfunction "2_2") (pintype "passive"))
      (node (ref "U4") (pin "1") (pinfunction "VBATT(P1)_1") (pintype "bidirectional"))
    )
    (net (code "57") (name "Net-(U5-1A)") (class "Default")
      (node (ref "C29") (pin "1") (pinfunction "1_1") (pintype "passive"))
      (node (ref "R34") (pin "2") (pinfunction "2_2") (pintype "passive"))
      (node (ref "U5") (pin "P$1") (pinfunction "1A_P$1") (pintype "bidirectional"))
    )
    (net (code "58") (name "Net-(U5-2A)") (class "Default")
      (node (ref "C28") (pin "1") (pinfunction "1_1") (pintype "passive"))
      (node (ref "R35") (pin "2") (pinfunction "2_2") (pintype "passive"))
      (node (ref "U5") (pin "P$3") (pinfunction "2A_P$3") (pintype "bidirectional"))
    )
    (net (code "59") (name "Net-(U5-3A)") (class "Default")
      (node (ref "C27") (pin "1") (pinfunction "1_1") (pintype "passive"))
      (node (ref "R36") (pin "2") (pinfunction "2_2") (pintype "passive"))
      (node (ref "U5") (pin "P$5") (pinfunction "3A_P$5") (pintype "bidirectional"))
    )
    (net (code "60") (name "Net-(U5-4A)") (class "Default")
      (node (ref "C26") (pin "1") (pinfunction "1_1") (pintype "passive"))
      (node (ref "R37") (pin "1") (pinfunction "1_1") (pintype "passive"))
      (node (ref "U5") (pin "P$9") (pinfunction "4A_P$9") (pintype "bidirectional"))
    )
    (net (code "61") (name "Net-(U5-5A)") (class "Default")
      (node (ref "C25") (pin "1") (pinfunction "1_1") (pintype "passive"))
      (node (ref "R38") (pin "1") (pinfunction "1_1") (pintype "passive"))
      (node (ref "U5") (pin "P$11") (pinfunction "5A_P$11") (pintype "bidirectional"))
    )
    (net (code "62") (name "Net-(X2-2)") (class "Default")
      (node (ref "C23") (pin "2") (pinfunction "2_2") (pintype "passive"))
      (node (ref "R21") (pin "1") (pinfunction "1_1") (pintype "passive"))
      (node (ref "X2") (pin "P$03") (pinfunction "2_P$03") (pintype "bidirectional"))
    )
    (net (code "63") (name "V+_CHG") (class "Default")
      (node (ref "C15") (pin "1") (pinfunction "1_1") (pintype "passive"))
      (node (ref "CONN1") (pin "VCC") (pinfunction "VCC_VCC") (pintype "bidirectional"))
      (node (ref "R2") (pin "1") (pinfunction "1_1") (pintype "passive"))
      (node (ref "R24") (pin "2") (pinfunction "2_2") (pintype "passive"))
      (node (ref "U1") (pin "VDD") (pinfunction "VDD_VDD") (pintype "power_in"))
      (node (ref "U1") (pin "VDD2") (pinfunction "VDD2_VDD2") (pintype "bidirectional"))
    )
    (net (code "64") (name "VBATT+") (class "Default")
      (node (ref "C1") (pin "1") (pinfunction "1_1") (pintype "passive"))
      (node (ref "C16") (pin "1") (pinfunction "1_1") (pintype "passive"))
      (node (ref "C3") (pin "1") (pinfunction "1_1") (pintype "passive"))
      (node (ref "CN1") (pin "1") (pinfunction "2_1") (pintype "passive"))
      (node (ref "Q1") (pin "2") (pinfunction "S2_2") (pintype "bidirectional"))
      (node (ref "R11") (pin "2") (pinfunction "2_2") (pintype "passive"))
      (node (ref "R12") (pin "2") (pinfunction "2_2") (pintype "passive"))
      (node (ref "R16") (pin "2") (pinfunction "2_2") (pintype "passive"))
      (node (ref "U1") (pin "VBATT") (pinfunction "VBATT_VBATT") (pintype "bidirectional"))
      (node (ref "U1") (pin "VBATT2") (pinfunction "VBATT2_VBATT2") (pintype "bidirectional"))
      (node (ref "U3") (pin "VIN") (pinfunction "VIN_VIN") (pintype "bidirectional"))
    )
    (net (code "65") (name "VBATT+_SW") (class "Default")
      (node (ref "C5") (pin "1") (pinfunction "1_1") (pintype "passive"))
      (node (ref "JP5") (pin "3") (pinfunction "3_3") (pintype "passive"))
      (node (ref "Q1") (pin "4") (pinfunction "D2_4") (pintype "bidirectional"))
      (node (ref "R14") (pin "2") (pinfunction "2_2") (pintype "passive"))
      (node (ref "R15") (pin "1") (pinfunction "1_1") (pintype "passive"))
      (node (ref "R29") (pin "2") (pinfunction "2_2") (pintype "passive"))
      (node (ref "U2") (pin "1") (pinfunction "A_1") (pintype "bidirectional"))
      (node (ref "U2") (pin "5") (pinfunction "VCC_5") (pintype "bidirectional"))
    )
    (net (code "66") (name "unconnected-(JP1-Pad3)") (class "Default")
      (node (ref "JP1") (pin "3") (pinfunction "3_3") (pintype "passive"))
    )
    (net (code "67") (name "unconnected-(U5-6Y-PadP$12)") (class "Default")
      (node (ref "U5") (pin "P$12") (pinfunction "6Y_P$12") (pintype "bidirectional"))
    )
  )
)
